# Sheet2.net
KiCad netlist of a schematic drawn in Altium Designer
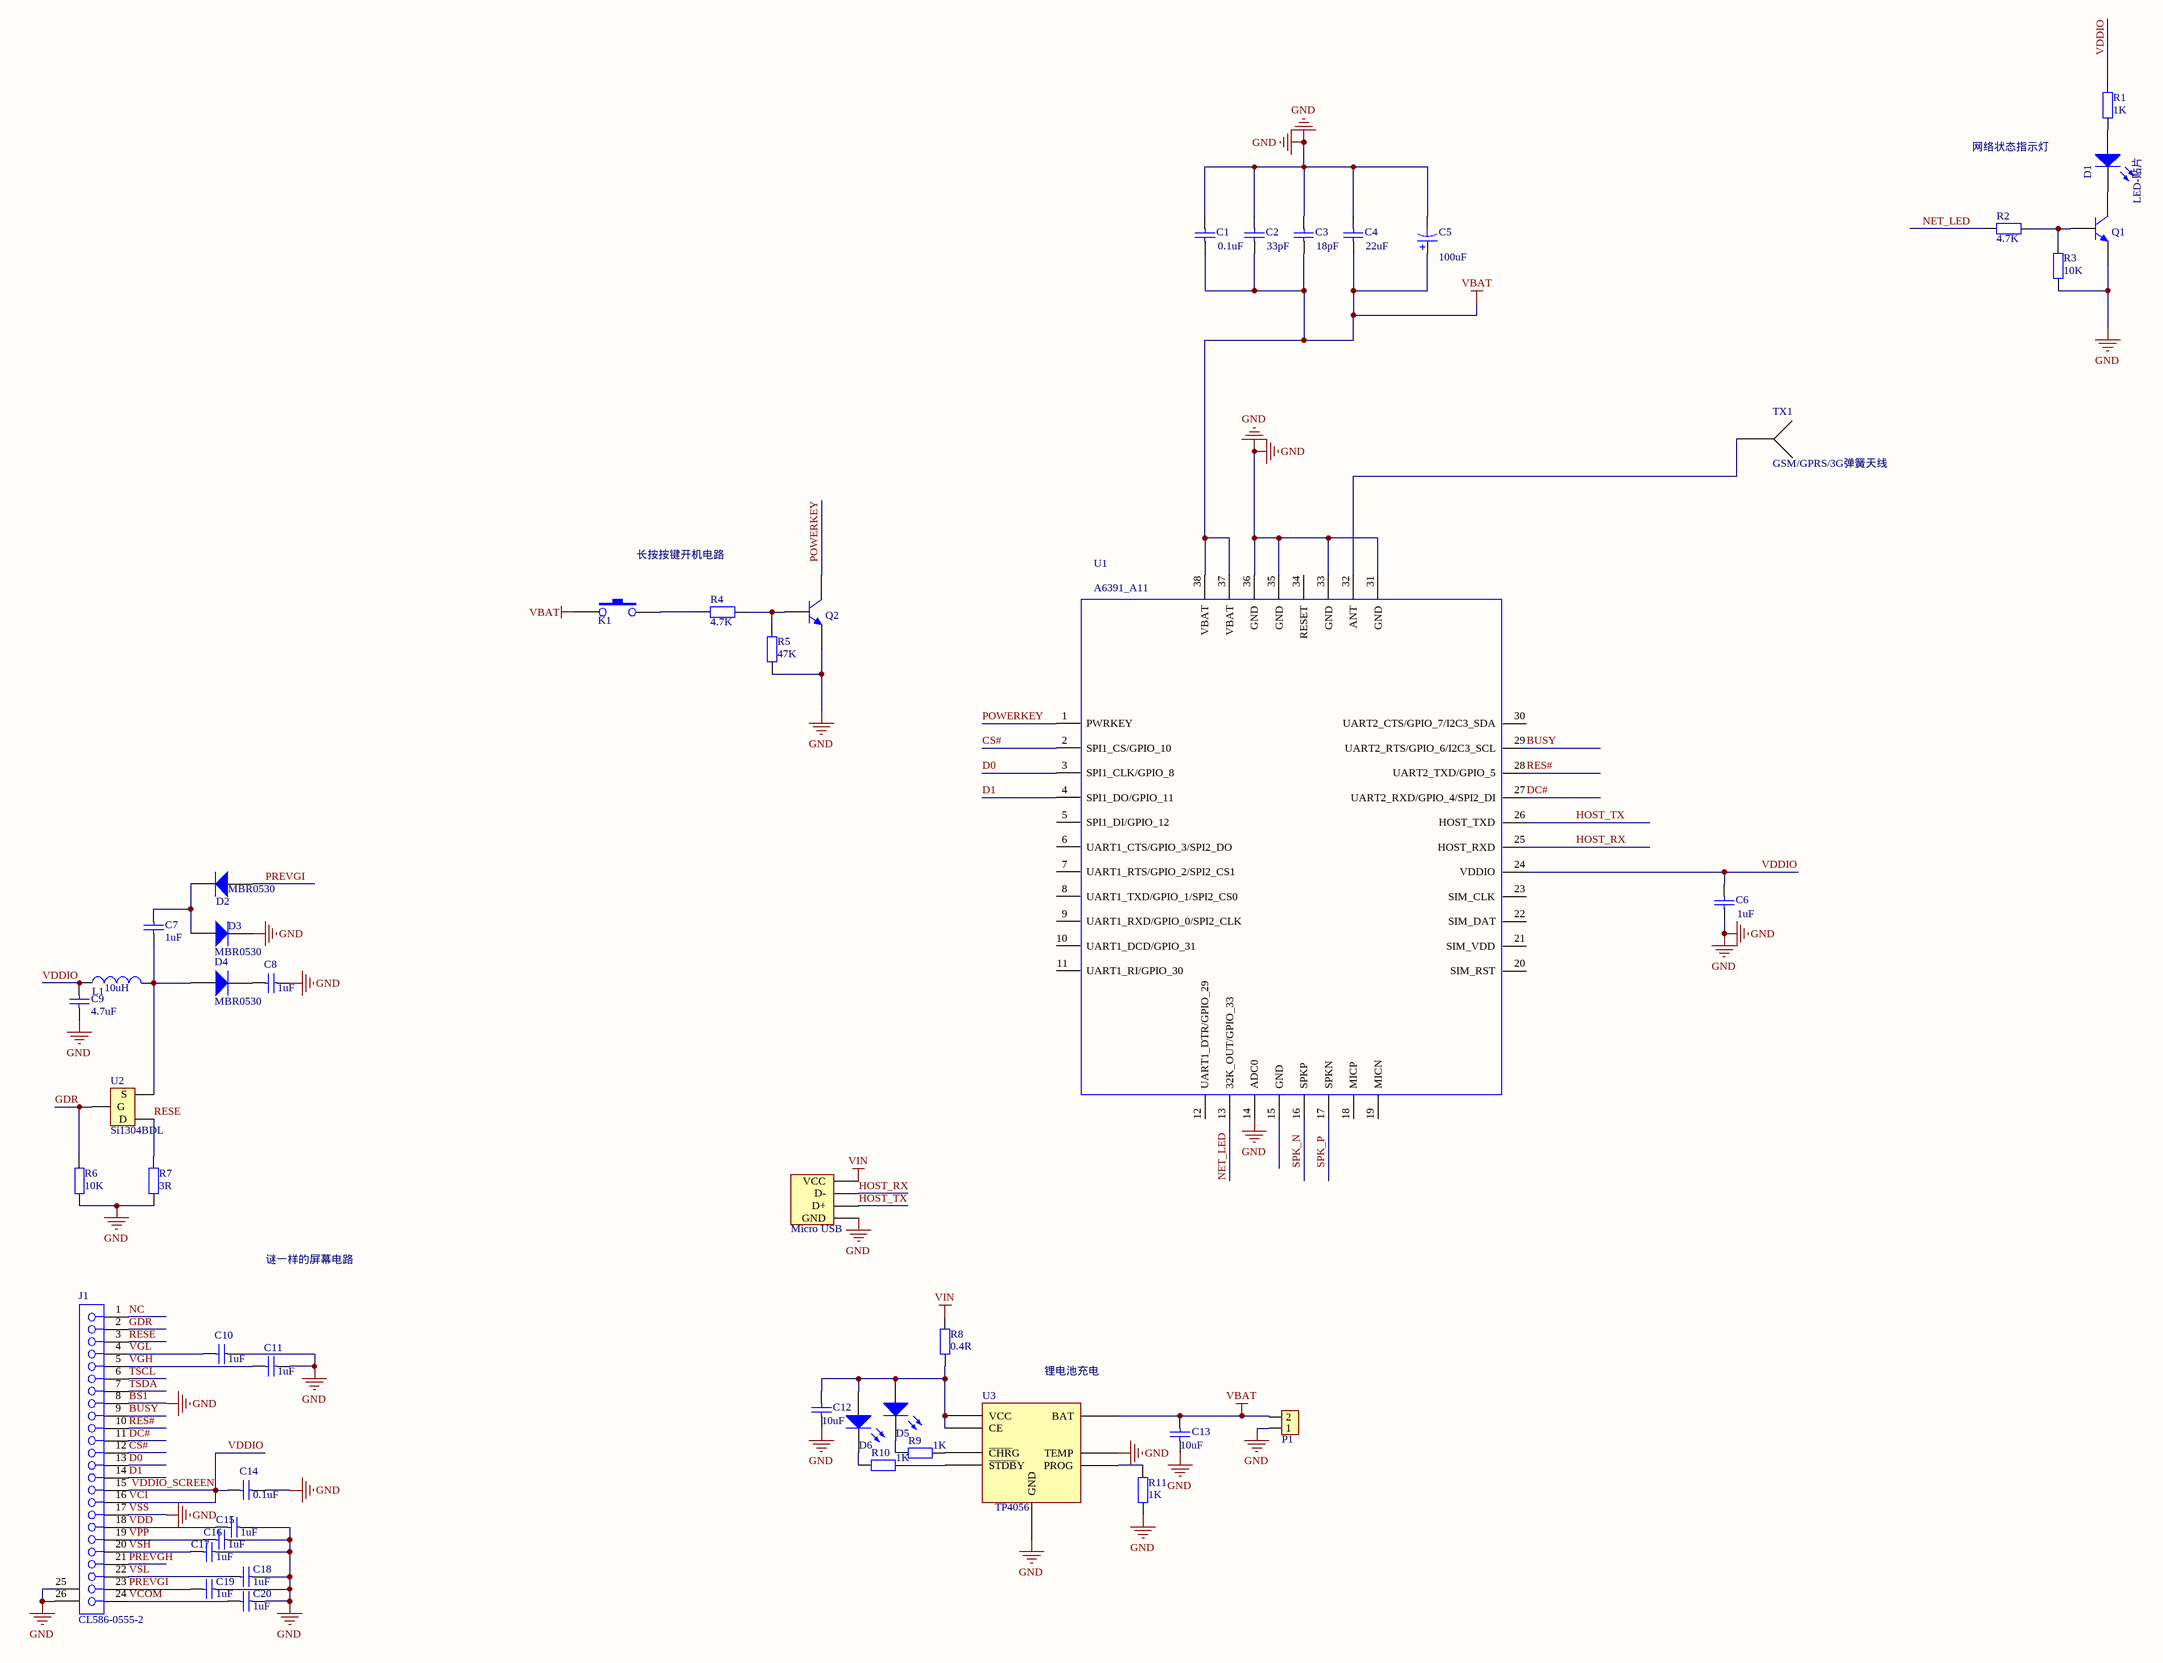
[diagram p0: Sheet2.SchDoc]

(export (version "E")
  (design (tool "Eeschema 10.0.6"))
  (components
    (comp (ref "C1")
      (value "0.1uF")
      (footprint "0603AC")
      (description "0603;0.1uF")
      (fields (field (name "Comment") "无极性电容") (field (name "PUBLISHER") "Altium Limited"))
      (libsource (lib "Schlib2") (part "无极性电容"))
    )
    (comp (ref "C2")
      (value "33pF")
      (footprint "0603AC")
      (description "0603;33pF")
      (fields (field (name "Comment") "无极性电容") (field (name "PUBLISHER") "Altium Limited"))
      (libsource (lib "Schlib2") (part "无极性电容"))
    )
    (comp (ref "C3")
      (value "18pF")
      (footprint "0603AC")
      (description "0603;18pF")
      (fields (field (name "Comment") "无极性电容") (field (name "PUBLISHER") "Altium Limited"))
      (libsource (lib "Schlib2") (part "无极性电容"))
    )
    (comp (ref "C4")
      (value "22uF")
      (footprint "0603AC")
      (description "0603;22pF")
      (fields (field (name "Comment") "无极性电容") (field (name "PUBLISHER") "Altium Limited"))
      (libsource (lib "Schlib2") (part "无极性电容"))
    )
    (comp (ref "C5")
      (value "100uF")
      (footprint "CAPM-B-3528X21N")
      (description "Polarized Capacitor (Axial)")
      (fields (field (name "Comment") "贴片铝/钽电容") (field (name "PUBLISHER") "Altium Limited"))
      (libsource (lib "Schlib2") (part "贴片铝/钽电容"))
    )
    (comp (ref "C6")
      (value "1uF")
      (footprint "0603AC")
      (description "0603;1uF")
      (fields (field (name "Comment") "无极性电容") (field (name "PUBLISHER") "Altium Limited"))
      (libsource (lib "Schlib2") (part "无极性电容"))
    )
    (comp (ref "C7")
      (value "1uF")
      (footprint "0603AC")
      (description "Capacitor")
      (fields (field (name "Comment") "无极性电容") (field (name "PUBLISHER") "Altium Limited"))
      (libsource (lib "Schlib1") (part "无极性电容"))
    )
    (comp (ref "C8")
      (value "1uF")
      (footprint "0603AC")
      (description "Capacitor")
      (fields (field (name "Comment") "无极性电容") (field (name "PUBLISHER") "Altium Limited"))
      (libsource (lib "Schlib1") (part "无极性电容"))
    )
    (comp (ref "C9")
      (value "4.7uF")
      (footprint "0603AC")
      (description "Capacitor")
      (fields (field (name "Comment") "无极性电容") (field (name "PUBLISHER") "Altium Limited"))
      (libsource (lib "Schlib1") (part "无极性电容"))
    )
    (comp (ref "C10")
      (value "1uF")
      (footprint "0603AC")
      (description "Capacitor")
      (fields (field (name "Comment") "无极性电容") (field (name "PUBLISHER") "Altium Limited"))
      (libsource (lib "Schlib1") (part "无极性电容"))
    )
    (comp (ref "C11")
      (value "1uF")
      (footprint "0603AC")
      (description "Capacitor")
      (fields (field (name "Comment") "无极性电容") (field (name "PUBLISHER") "Altium Limited"))
      (libsource (lib "Schlib1") (part "无极性电容"))
    )
    (comp (ref "C12")
      (value "10uF")
      (footprint "0603AC")
      (description "Capacitor")
      (fields (field (name "Comment") "无极性电容") (field (name "PUBLISHER") "Altium Limited"))
      (libsource (lib "Schlib1") (part "无极性电容"))
    )
    (comp (ref "C13")
      (value "10uF")
      (footprint "0603AC")
      (description "Capacitor")
      (fields (field (name "Comment") "无极性电容") (field (name "PUBLISHER") "Altium Limited"))
      (libsource (lib "Schlib1") (part "无极性电容"))
    )
    (comp (ref "C14")
      (value "0.1uF")
      (footprint "0603AC")
      (description "Capacitor")
      (fields (field (name "Comment") "无极性电容") (field (name "PUBLISHER") "Altium Limited"))
      (libsource (lib "Schlib1") (part "无极性电容"))
    )
    (comp (ref "C15")
      (value "1uF")
      (footprint "0603AC")
      (description "Capacitor")
      (fields (field (name "Comment") "无极性电容") (field (name "PUBLISHER") "Altium Limited"))
      (libsource (lib "Schlib1") (part "无极性电容"))
    )
    (comp (ref "C16")
      (value "1uF")
      (footprint "0603AC")
      (description "Capacitor")
      (fields (field (name "Comment") "无极性电容") (field (name "PUBLISHER") "Altium Limited"))
      (libsource (lib "Schlib1") (part "无极性电容"))
    )
    (comp (ref "C17")
      (value "1uF")
      (footprint "0603AC")
      (description "Capacitor")
      (fields (field (name "Comment") "无极性电容") (field (name "PUBLISHER") "Altium Limited"))
      (libsource (lib "Schlib1") (part "无极性电容"))
    )
    (comp (ref "C18")
      (value "1uF")
      (footprint "0603AC")
      (description "Capacitor")
      (fields (field (name "Comment") "无极性电容") (field (name "PUBLISHER") "Altium Limited"))
      (libsource (lib "Schlib1") (part "无极性电容"))
    )
    (comp (ref "C19")
      (value "1uF")
      (footprint "0603AC")
      (description "Capacitor")
      (fields (field (name "Comment") "无极性电容") (field (name "PUBLISHER") "Altium Limited"))
      (libsource (lib "Schlib1") (part "无极性电容"))
    )
    (comp (ref "C20")
      (value "1uF")
      (footprint "0603AC")
      (description "Capacitor")
      (fields (field (name "Comment") "无极性电容") (field (name "PUBLISHER") "Altium Limited"))
      (libsource (lib "Schlib1") (part "无极性电容"))
    )
    (comp (ref "D1")
      (value "LED-贴片")
      (footprint "LED_0603")
      (description "0603;LED")
      (libsource (lib "Schlib2") (part "LED-贴片-直插"))
    )
    (comp (ref "D2") (value "MBR0530") (footprint "SOD123") (libsource (lib "Schlib1") (part "二极管")))
    (comp (ref "D3") (value "MBR0530") (footprint "SOD123") (libsource (lib "Schlib1") (part "二极管")))
    (comp (ref "D4") (value "MBR0530") (footprint "SOD123") (libsource (lib "Schlib1") (part "二极管")))
    (comp (ref "D5")
      (value "LED-贴片-直插")
      (footprint "LED_0603")
      (libsource (lib "Schlib1") (part "LED-贴片-直插"))
    )
    (comp (ref "D6")
      (value "LED-贴片-直插")
      (footprint "LED_0603")
      (libsource (lib "Schlib1") (part "LED-贴片-直插"))
    )
    (comp (ref "J1")
      (value "CL586-0555-2")
      (footprint "FH12-24S-0.5SH")
      (description "FH12 Series, \"Flip-Lock\" SMT/ZIF Connector - 0.5mm Spaced Top Contact")
      (fields (field (name "PUBLISHER") "Altium Limited"))
      (libsource (lib "HRS FPC-FFC FH12 Series") (part "CL586-0555-2"))
    )
    (comp (ref "K1") (value "KEY") (footprint "KEY_4*4") (libsource (lib "Schlib1") (part "KEY")))
    (comp (ref "L1")
      (value "10uH")
      (footprint "3225")
      (fields (field (name "Comment") "LND"))
      (libsource (lib "Schlib1") (part "LND"))
    )
    (comp (ref "Micro USB")
      (value "Micro USB-B")
      (footprint "Micro USB")
      (libsource (lib "Schlib1") (part "Micro USB-B"))
    )
    (comp (ref "P1")
      (value "Header 2")
      (footprint "Header 2")
      (description "DIP 2.54")
      (libsource (lib "Schlib1") (part "Header 2_1"))
    )
    (comp (ref "Q1")
      (value "NPN")
      (footprint "SOT95P230X110-3N")
      (description "NPN;SOT95P230X110-3N")
      (libsource (lib "Schlib2") (part "NPN_1"))
    )
    (comp (ref "Q2")
      (value "NPN")
      (footprint "SOT95P230X110-3N")
      (description "NPN;SOT95P230X110-3N")
      (libsource (lib "Schlib2") (part "NPN_1"))
    )
    (comp (ref "R1")
      (value "1K")
      (footprint "0603AR")
      (description "0603;1K")
      (fields (field (name "Comment") "贴片电阻") (field (name "PUBLISHER") "Altium Limited"))
      (libsource (lib "") (part "贴片电阻_2"))
    )
    (comp (ref "R2")
      (value "4.7K")
      (footprint "0603AR")
      (description "0603;4.7K")
      (fields (field (name "Comment") "贴片电阻") (field (name "PUBLISHER") "Altium Limited"))
      (libsource (lib "") (part "贴片电阻_1"))
    )
    (comp (ref "R3")
      (value "10K")
      (footprint "0603AR")
      (description "0603;10K")
      (fields (field (name "Comment") "贴片电阻") (field (name "PUBLISHER") "Altium Limited"))
      (libsource (lib "Schlib2") (part "贴片电阻"))
    )
    (comp (ref "R4")
      (value "4.7K")
      (footprint "0603AR")
      (description "0603;4.7K")
      (fields (field (name "Comment") "贴片电阻") (field (name "PUBLISHER") "Altium Limited"))
      (libsource (lib "") (part "贴片电阻_1"))
    )
    (comp (ref "R5")
      (value "47K")
      (footprint "0603AR")
      (description "0603;10K")
      (fields (field (name "Comment") "贴片电阻") (field (name "PUBLISHER") "Altium Limited"))
      (libsource (lib "Schlib2") (part "贴片电阻"))
    )
    (comp (ref "R6")
      (value "10K")
      (footprint "0603AR")
      (description "0603;10K")
      (fields (field (name "Comment") "贴片电阻") (field (name "PUBLISHER") "Altium Limited"))
      (libsource (lib "Schlib2") (part "贴片电阻"))
    )
    (comp (ref "R7")
      (value "3R")
      (footprint "0603AR")
      (description "0603;10K")
      (fields (field (name "Comment") "贴片电阻") (field (name "PUBLISHER") "Altium Limited"))
      (libsource (lib "Schlib2") (part "贴片电阻"))
    )
    (comp (ref "R8")
      (value "0.4R")
      (footprint "0603AR")
      (description "Resistor")
      (fields (field (name "Comment") "贴片电阻") (field (name "PUBLISHER") "Altium Limited"))
      (libsource (lib "Schlib1") (part "贴片电阻"))
    )
    (comp (ref "R9")
      (value "1K")
      (footprint "0603AR")
      (description "Resistor")
      (fields (field (name "Comment") "贴片电阻") (field (name "PUBLISHER") "Altium Limited"))
      (libsource (lib "") (part "贴片电阻_2"))
    )
    (comp (ref "R10")
      (value "1K")
      (footprint "0603AR")
      (description "Resistor")
      (fields (field (name "Comment") "贴片电阻") (field (name "PUBLISHER") "Altium Limited"))
      (libsource (lib "") (part "贴片电阻_2"))
    )
    (comp (ref "R11")
      (value "1K")
      (footprint "0603AR")
      (description "Resistor")
      (fields (field (name "Comment") "贴片电阻") (field (name "PUBLISHER") "Altium Limited"))
      (libsource (lib "") (part "贴片电阻_1"))
    )
    (comp (ref "TX1")
      (value "GSM/GPRS/3G弹簧天线")
      (footprint "GSM/GPRS/3G弹簧天线")
      (libsource (lib "Schlib1") (part "GSM/GPRS/3G弹簧天线"))
    )
    (comp (ref "U1")
      (value "A6391_A11")
      (footprint "A6391_A11")
      (description "202芯片")
      (libsource (lib "Schlib2") (part "A6391_A11"))
    )
    (comp (ref "U2") (value "Si1304BDL") (footprint "AO3400") (libsource (lib "wodeku") (part "AO3400")))
    (comp (ref "U3") (value "TP4056") (footprint "SOP8LM386") (libsource (lib "Schlib1") (part "TP4056")))
  )
  (nets
    (net (code "1") (name "/BUSY") (class "Default")
      (node (ref "J1") (pin "9") (pinfunction "9_9") (pintype "passive"))
      (node (ref "U1") (pin "29") (pinfunction "UART2_RTS/GPIO_6/I2C3_SCL_29") (pintype "passive"))
    )
    (net (code "2") (name "/CS#") (class "Default")
      (node (ref "J1") (pin "12") (pinfunction "12_12") (pintype "passive"))
      (node (ref "U1") (pin "2") (pinfunction "SPI1_CS/GPIO_10_2") (pintype "passive"))
    )
    (net (code "3") (name "/D0") (class "Default")
      (node (ref "J1") (pin "13") (pinfunction "13_13") (pintype "passive"))
      (node (ref "U1") (pin "3") (pinfunction "SPI1_CLK/GPIO_8_3") (pintype "passive"))
    )
    (net (code "4") (name "/D1") (class "Default")
      (node (ref "J1") (pin "14") (pinfunction "14_14") (pintype "passive"))
      (node (ref "U1") (pin "4") (pinfunction "SPI1_DO/GPIO_11_4") (pintype "passive"))
    )
    (net (code "5") (name "/DC#") (class "Default")
      (node (ref "J1") (pin "11") (pinfunction "11_11") (pintype "passive"))
      (node (ref "U1") (pin "27") (pinfunction "UART2_RXD/GPIO_4/SPI2_DI_27") (pintype "passive"))
    )
    (net (code "6") (name "/GDR") (class "Default")
      (node (ref "J1") (pin "2") (pinfunction "2_2") (pintype "passive"))
      (node (ref "R6") (pin "1") (pinfunction "1_1") (pintype "passive"))
      (node (ref "U2") (pin "1") (pinfunction "G_1") (pintype "passive"))
    )
    (net (code "7") (name "/HOST_RX") (class "Default")
      (node (ref "Micro USB") (pin "2") (pinfunction "D-_2") (pintype "passive"))
      (node (ref "U1") (pin "25") (pinfunction "HOST_RXD_25") (pintype "passive"))
    )
    (net (code "8") (name "/HOST_TX") (class "Default")
      (node (ref "Micro USB") (pin "3") (pinfunction "D+_3") (pintype "passive"))
      (node (ref "U1") (pin "26") (pinfunction "HOST_TXD_26") (pintype "passive"))
    )
    (net (code "9") (name "/NC") (class "Default")
      (node (ref "J1") (pin "1") (pinfunction "1_1") (pintype "passive"))
    )
    (net (code "10") (name "/NET_LED") (class "Default")
      (node (ref "R2") (pin "2") (pinfunction "2_2") (pintype "passive"))
      (node (ref "U1") (pin "13") (pinfunction "32K_OUT/GPIO_33_13") (pintype "passive"))
    )
    (net (code "11") (name "/POWERKEY") (class "Default")
      (node (ref "Q2") (pin "3") (pinfunction "C_3") (pintype "passive"))
      (node (ref "U1") (pin "1") (pinfunction "PWRKEY_1") (pintype "passive"))
    )
    (net (code "12") (name "/PREVGH") (class "Default")
      (node (ref "J1") (pin "21") (pinfunction "21_21") (pintype "passive"))
    )
    (net (code "13") (name "/PREVGI") (class "Default")
      (node (ref "C19") (pin "1") (pinfunction "1_1") (pintype "passive"))
      (node (ref "D2") (pin "1") (pinfunction "A_1") (pintype "passive"))
      (node (ref "J1") (pin "23") (pinfunction "23_23") (pintype "passive"))
    )
    (net (code "14") (name "/RES#") (class "Default")
      (node (ref "J1") (pin "10") (pinfunction "10_10") (pintype "passive"))
      (node (ref "U1") (pin "28") (pinfunction "UART2_TXD/GPIO_5_28") (pintype "passive"))
    )
    (net (code "15") (name "/RESE") (class "Default")
      (node (ref "J1") (pin "3") (pinfunction "3_3") (pintype "passive"))
      (node (ref "R7") (pin "1") (pinfunction "1_1") (pintype "passive"))
      (node (ref "U2") (pin "3") (pinfunction "D_3") (pintype "passive"))
    )
    (net (code "16") (name "/SPK_N") (class "Default")
      (node (ref "U1") (pin "16") (pinfunction "SPKP_16") (pintype "passive"))
    )
    (net (code "17") (name "/SPK_P") (class "Default")
      (node (ref "U1") (pin "17") (pinfunction "SPKN_17") (pintype "passive"))
    )
    (net (code "18") (name "/TSCL") (class "Default")
      (node (ref "J1") (pin "6") (pinfunction "6_6") (pintype "passive"))
    )
    (net (code "19") (name "/TSDA") (class "Default")
      (node (ref "J1") (pin "7") (pinfunction "7_7") (pintype "passive"))
    )
    (net (code "20") (name "/VCI") (class "Default")
      (node (ref "C14") (pin "1") (pinfunction "1_1") (pintype "passive"))
      (node (ref "C6") (pin "1") (pinfunction "1_1") (pintype "passive"))
      (node (ref "C9") (pin "2") (pinfunction "2_2") (pintype "passive"))
      (node (ref "J1") (pin "15") (pinfunction "15_15") (pintype "passive"))
      (node (ref "J1") (pin "16") (pinfunction "16_16") (pintype "passive"))
      (node (ref "L1") (pin "1") (pinfunction "1_1") (pintype "passive"))
      (node (ref "R1") (pin "2") (pinfunction "2_2") (pintype "passive"))
      (node (ref "U1") (pin "24") (pinfunction "VDDIO_24") (pintype "passive"))
    )
    (net (code "21") (name "/VCOM") (class "Default")
      (node (ref "C20") (pin "1") (pinfunction "1_1") (pintype "passive"))
      (node (ref "J1") (pin "24") (pinfunction "24_24") (pintype "passive"))
    )
    (net (code "22") (name "/VDD") (class "Default")
      (node (ref "C15") (pin "1") (pinfunction "1_1") (pintype "passive"))
      (node (ref "J1") (pin "18") (pinfunction "18_18") (pintype "passive"))
    )
    (net (code "23") (name "/VGH") (class "Default")
      (node (ref "C11") (pin "1") (pinfunction "1_1") (pintype "passive"))
      (node (ref "J1") (pin "5") (pinfunction "5_5") (pintype "passive"))
    )
    (net (code "24") (name "/VGL") (class "Default")
      (node (ref "C10") (pin "1") (pinfunction "1_1") (pintype "passive"))
      (node (ref "J1") (pin "4") (pinfunction "4_4") (pintype "passive"))
    )
    (net (code "25") (name "/VPP") (class "Default")
      (node (ref "C16") (pin "1") (pinfunction "1_1") (pintype "passive"))
      (node (ref "J1") (pin "19") (pinfunction "19_19") (pintype "passive"))
    )
    (net (code "26") (name "/VSH") (class "Default")
      (node (ref "C17") (pin "1") (pinfunction "1_1") (pintype "passive"))
      (node (ref "J1") (pin "20") (pinfunction "20_20") (pintype "passive"))
    )
    (net (code "27") (name "/VSL") (class "Default")
      (node (ref "C18") (pin "1") (pinfunction "1_1") (pintype "passive"))
      (node (ref "J1") (pin "22") (pinfunction "22_22") (pintype "passive"))
    )
    (net (code "28") (name "GND") (class "Default")
      (node (ref "C1") (pin "1") (pinfunction "1_1") (pintype "passive"))
      (node (ref "C10") (pin "2") (pinfunction "2_2") (pintype "passive"))
      (node (ref "C11") (pin "2") (pinfunction "2_2") (pintype "passive"))
      (node (ref "C12") (pin "1") (pinfunction "1_1") (pintype "passive"))
      (node (ref "C13") (pin "1") (pinfunction "1_1") (pintype "passive"))
      (node (ref "C14") (pin "2") (pinfunction "2_2") (pintype "passive"))
      (node (ref "C15") (pin "2") (pinfunction "2_2") (pintype "passive"))
      (node (ref "C16") (pin "2") (pinfunction "2_2") (pintype "passive"))
      (node (ref "C17") (pin "2") (pinfunction "2_2") (pintype "passive"))
      (node (ref "C18") (pin "2") (pinfunction "2_2") (pintype "passive"))
      (node (ref "C19") (pin "2") (pinfunction "2_2") (pintype "passive"))
      (node (ref "C2") (pin "1") (pinfunction "1_1") (pintype "passive"))
      (node (ref "C20") (pin "2") (pinfunction "2_2") (pintype "passive"))
      (node (ref "C3") (pin "1") (pinfunction "1_1") (pintype "passive"))
      (node (ref "C4") (pin "1") (pinfunction "1_1") (pintype "passive"))
      (node (ref "C5") (pin "2") (pinfunction "2_2") (pintype "passive"))
      (node (ref "C6") (pin "2") (pinfunction "2_2") (pintype "passive"))
      (node (ref "C8") (pin "2") (pinfunction "2_2") (pintype "passive"))
      (node (ref "C9") (pin "1") (pinfunction "1_1") (pintype "passive"))
      (node (ref "D3") (pin "2") (pinfunction "K_2") (pintype "passive"))
      (node (ref "J1") (pin "17") (pinfunction "17_17") (pintype "passive"))
      (node (ref "J1") (pin "25") (pinfunction "MH1_25") (pintype "passive"))
      (node (ref "J1") (pin "26") (pinfunction "MH2_26") (pintype "passive"))
      (node (ref "J1") (pin "8") (pinfunction "8_8") (pintype "passive"))
      (node (ref "Micro USB") (pin "4") (pinfunction "GND_4") (pintype "passive"))
      (node (ref "P1") (pin "1") (pinfunction "1_1") (pintype "passive"))
      (node (ref "Q1") (pin "2") (pinfunction "E_2") (pintype "passive"))
      (node (ref "Q2") (pin "2") (pinfunction "E_2") (pintype "passive"))
      (node (ref "R11") (pin "2") (pinfunction "2_2") (pintype "passive"))
      (node (ref "R3") (pin "2") (pinfunction "2_2") (pintype "passive"))
      (node (ref "R5") (pin "2") (pinfunction "2_2") (pintype "passive"))
      (node (ref "R6") (pin "2") (pinfunction "2_2") (pintype "passive"))
      (node (ref "R7") (pin "2") (pinfunction "2_2") (pintype "passive"))
      (node (ref "U1") (pin "14") (pinfunction "ADC0_14") (pintype "passive"))
      (node (ref "U1") (pin "31") (pinfunction "GND_31") (pintype "passive"))
      (node (ref "U1") (pin "33") (pinfunction "GND_33") (pintype "passive"))
      (node (ref "U1") (pin "35") (pinfunction "GND_35") (pintype "passive"))
      (node (ref "U1") (pin "36") (pinfunction "GND_36") (pintype "passive"))
      (node (ref "U1") (pin "39") (pinfunction "GND_39") (pintype "power_in"))
      (node (ref "U1") (pin "40") (pinfunction "GND_40") (pintype "power_in"))
      (node (ref "U1") (pin "41") (pinfunction "GND_41") (pintype "power_in"))
      (node (ref "U3") (pin "1") (pinfunction "TEMP_1") (pintype "passive"))
      (node (ref "U3") (pin "3") (pinfunction "GND_3") (pintype "passive"))
    )
    (net (code "29") (name "Net-(D1-A)") (class "Default")
      (node (ref "D1") (pin "1") (pinfunction "A_1") (pintype "passive"))
      (node (ref "R1") (pin "1") (pinfunction "1_1") (pintype "passive"))
    )
    (net (code "30") (name "Net-(D1-K)") (class "Default")
      (node (ref "D1") (pin "2") (pinfunction "K_2") (pintype "passive"))
      (node (ref "Q1") (pin "3") (pinfunction "C_3") (pintype "passive"))
    )
    (net (code "31") (name "Net-(D2-K)") (class "Default")
      (node (ref "C7") (pin "2") (pinfunction "2_2") (pintype "passive"))
      (node (ref "D2") (pin "2") (pinfunction "K_2") (pintype "passive"))
      (node (ref "D3") (pin "1") (pinfunction "A_1") (pintype "passive"))
    )
    (net (code "32") (name "Net-(D4-A)") (class "Default")
      (node (ref "C7") (pin "1") (pinfunction "1_1") (pintype "passive"))
      (node (ref "D4") (pin "1") (pinfunction "A_1") (pintype "passive"))
      (node (ref "L1") (pin "2") (pinfunction "2_2") (pintype "passive"))
      (node (ref "U2") (pin "2") (pinfunction "S_2") (pintype "passive"))
    )
    (net (code "33") (name "Net-(D4-K)") (class "Default")
      (node (ref "C8") (pin "1") (pinfunction "1_1") (pintype "passive"))
      (node (ref "D4") (pin "2") (pinfunction "K_2") (pintype "passive"))
    )
    (net (code "34") (name "Net-(D5-A)") (class "Default")
      (node (ref "C12") (pin "2") (pinfunction "2_2") (pintype "passive"))
      (node (ref "D5") (pin "1") (pinfunction "A_1") (pintype "passive"))
      (node (ref "D6") (pin "1") (pinfunction "A_1") (pintype "passive"))
      (node (ref "R8") (pin "1") (pinfunction "1_1") (pintype "passive"))
      (node (ref "U3") (pin "4") (pinfunction "VCC_4") (pintype "passive"))
      (node (ref "U3") (pin "8") (pinfunction "CE_8") (pintype "passive"))
    )
    (net (code "35") (name "Net-(D5-K)") (class "Default")
      (node (ref "D5") (pin "2") (pinfunction "K_2") (pintype "passive"))
      (node (ref "R9") (pin "2") (pinfunction "2_2") (pintype "passive"))
    )
    (net (code "36") (name "Net-(D6-K)") (class "Default")
      (node (ref "D6") (pin "2") (pinfunction "K_2") (pintype "passive"))
      (node (ref "R10") (pin "2") (pinfunction "2_2") (pintype "passive"))
    )
    (net (code "37") (name "Net-(K1-Pad2)") (class "Default")
      (node (ref "K1") (pin "2") (pinfunction "2_2") (pintype "passive"))
      (node (ref "R4") (pin "2") (pinfunction "2_2") (pintype "passive"))
    )
    (net (code "38") (name "Net-(Q1-B)") (class "Default")
      (node (ref "Q1") (pin "1") (pinfunction "B_1") (pintype "passive"))
      (node (ref "R2") (pin "1") (pinfunction "1_1") (pintype "passive"))
      (node (ref "R3") (pin "1") (pinfunction "1_1") (pintype "passive"))
    )
    (net (code "39") (name "Net-(Q2-B)") (class "Default")
      (node (ref "Q2") (pin "1") (pinfunction "B_1") (pintype "passive"))
      (node (ref "R4") (pin "1") (pinfunction "1_1") (pintype "passive"))
      (node (ref "R5") (pin "1") (pinfunction "1_1") (pintype "passive"))
    )
    (net (code "40") (name "Net-(U1-ANT)") (class "Default")
      (node (ref "TX1") (pin "1") (pinfunction "1_1") (pintype "passive"))
      (node (ref "U1") (pin "32") (pinfunction "ANT_32") (pintype "passive"))
    )
    (net (code "41") (name "Net-(U3-PROG)") (class "Default")
      (node (ref "R11") (pin "1") (pinfunction "1_1") (pintype "passive"))
      (node (ref "U3") (pin "2") (pinfunction "PROG_2") (pintype "passive"))
    )
    (net (code "42") (name "Net-(U3-~{CHR}G)") (class "Default")
      (node (ref "R9") (pin "1") (pinfunction "1_1") (pintype "passive"))
      (node (ref "U3") (pin "7") (pinfunction "~{CHR}G_7") (pintype "passive"))
    )
    (net (code "43") (name "Net-(U3-~{STDB}Y)") (class "Default")
      (node (ref "R10") (pin "1") (pinfunction "1_1") (pintype "passive"))
      (node (ref "U3") (pin "6") (pinfunction "~{STDB}Y_6") (pintype "passive"))
    )
    (net (code "44") (name "VBAT") (class "Default")
      (node (ref "C1") (pin "2") (pinfunction "2_2") (pintype "passive"))
      (node (ref "C13") (pin "2") (pinfunction "2_2") (pintype "passive"))
      (node (ref "C2") (pin "2") (pinfunction "2_2") (pintype "passive"))
      (node (ref "C3") (pin "2") (pinfunction "2_2") (pintype "passive"))
      (node (ref "C4") (pin "2") (pinfunction "2_2") (pintype "passive"))
      (node (ref "C5") (pin "1") (pinfunction "1_1") (pintype "passive"))
      (node (ref "K1") (pin "1") (pinfunction "1_1") (pintype "passive"))
      (node (ref "P1") (pin "2") (pinfunction "2_2") (pintype "passive"))
      (node (ref "U1") (pin "37") (pinfunction "VBAT_37") (pintype "passive"))
      (node (ref "U1") (pin "38") (pinfunction "VBAT_38") (pintype "passive"))
      (node (ref "U3") (pin "5") (pinfunction "BAT_5") (pintype "passive"))
    )
    (net (code "45") (name "VIN") (class "Default")
      (node (ref "Micro USB") (pin "1") (pinfunction "VCC_1") (pintype "passive"))
      (node (ref "R8") (pin "2") (pinfunction "2_2") (pintype "passive"))
    )
    (net (code "46") (name "unconnected-(U1-GND-Pad15)") (class "Default")
      (node (ref "U1") (pin "15") (pinfunction "GND_15") (pintype "passive"))
    )
    (net (code "47") (name "unconnected-(U1-MICN-Pad19)") (class "Default")
      (node (ref "U1") (pin "19") (pinfunction "MICN_19") (pintype "passive"))
    )
    (net (code "48") (name "unconnected-(U1-MICP-Pad18)") (class "Default")
      (node (ref "U1") (pin "18") (pinfunction "MICP_18") (pintype "passive"))
    )
    (net (code "49") (name "unconnected-(U1-RESET-Pad34)") (class "Default")
      (node (ref "U1") (pin "34") (pinfunction "RESET_34") (pintype "passive"))
    )
    (net (code "50") (name "unconnected-(U1-SIM_CLK-Pad23)") (class "Default")
      (node (ref "U1") (pin "23") (pinfunction "SIM_CLK_23") (pintype "passive"))
    )
    (net (code "51") (name "unconnected-(U1-SIM_DAT-Pad22)") (class "Default")
      (node (ref "U1") (pin "22") (pinfunction "SIM_DAT_22") (pintype "passive"))
    )
    (net (code "52") (name "unconnected-(U1-SIM_RST-Pad20)") (class "Default")
      (node (ref "U1") (pin "20") (pinfunction "SIM_RST_20") (pintype "passive"))
    )
    (net (code "53") (name "unconnected-(U1-SIM_VDD-Pad21)") (class "Default")
      (node (ref "U1") (pin "21") (pinfunction "SIM_VDD_21") (pintype "passive"))
    )
    (net (code "54") (name "unconnected-(U1-SPI1_DI{slash}GPIO_12-Pad5)") (class "Default")
      (node (ref "U1") (pin "5") (pinfunction "SPI1_DI/GPIO_12_5") (pintype "passive"))
    )
    (net (code "55") (name "unconnected-(U1-UART1_CTS{slash}GPIO_3{slash}SPI2_DO-Pad6)") (class "Default")
      (node (ref "U1") (pin "6") (pinfunction "UART1_CTS/GPIO_3/SPI2_DO_6") (pintype "passive"))
    )
    (net (code "56") (name "unconnected-(U1-UART1_DCD{slash}GPIO_31-Pad10)") (class "Default")
      (node (ref "U1") (pin "10") (pinfunction "UART1_DCD/GPIO_31_10") (pintype "passive"))
    )
    (net (code "57") (name "unconnected-(U1-UART1_DTR{slash}GPIO_29-Pad12)") (class "Default")
      (node (ref "U1") (pin "12") (pinfunction "UART1_DTR/GPIO_29_12") (pintype "passive"))
    )
    (net (code "58") (name "unconnected-(U1-UART1_RI{slash}GPIO_30-Pad11)") (class "Default")
      (node (ref "U1") (pin "11") (pinfunction "UART1_RI/GPIO_30_11") (pintype "passive"))
    )
    (net (code "59") (name "unconnected-(U1-UART1_RTS{slash}GPIO_2{slash}SPI2_CS1-Pad7)") (class "Default")
      (node (ref "U1") (pin "7") (pinfunction "UART1_RTS/GPIO_2/SPI2_CS1_7") (pintype "passive"))
    )
    (net (code "60") (name "unconnected-(U1-UART1_RXD{slash}GPIO_0{slash}SPI2_CLK-Pad9)") (class "Default")
      (node (ref "U1") (pin "9") (pinfunction "UART1_RXD/GPIO_0/SPI2_CLK_9") (pintype "passive"))
    )
    (net (code "61") (name "unconnected-(U1-UART1_TXD{slash}GPIO_1{slash}SPI2_CS0-Pad8)") (class "Default")
      (node (ref "U1") (pin "8") (pinfunction "UART1_TXD/GPIO_1/SPI2_CS0_8") (pintype "passive"))
    )
    (net (code "62") (name "unconnected-(U1-UART2_CTS{slash}GPIO_7{slash}I2C3_SDA-Pad30)") (class "Default")
      (node (ref "U1") (pin "30") (pinfunction "UART2_CTS/GPIO_7/I2C3_SDA_30") (pintype "passive"))
    )
  )
)
